# INPUT_OUTPUT_BOTTOM.net
KiCad netlist of a schematic drawn in EAGLE
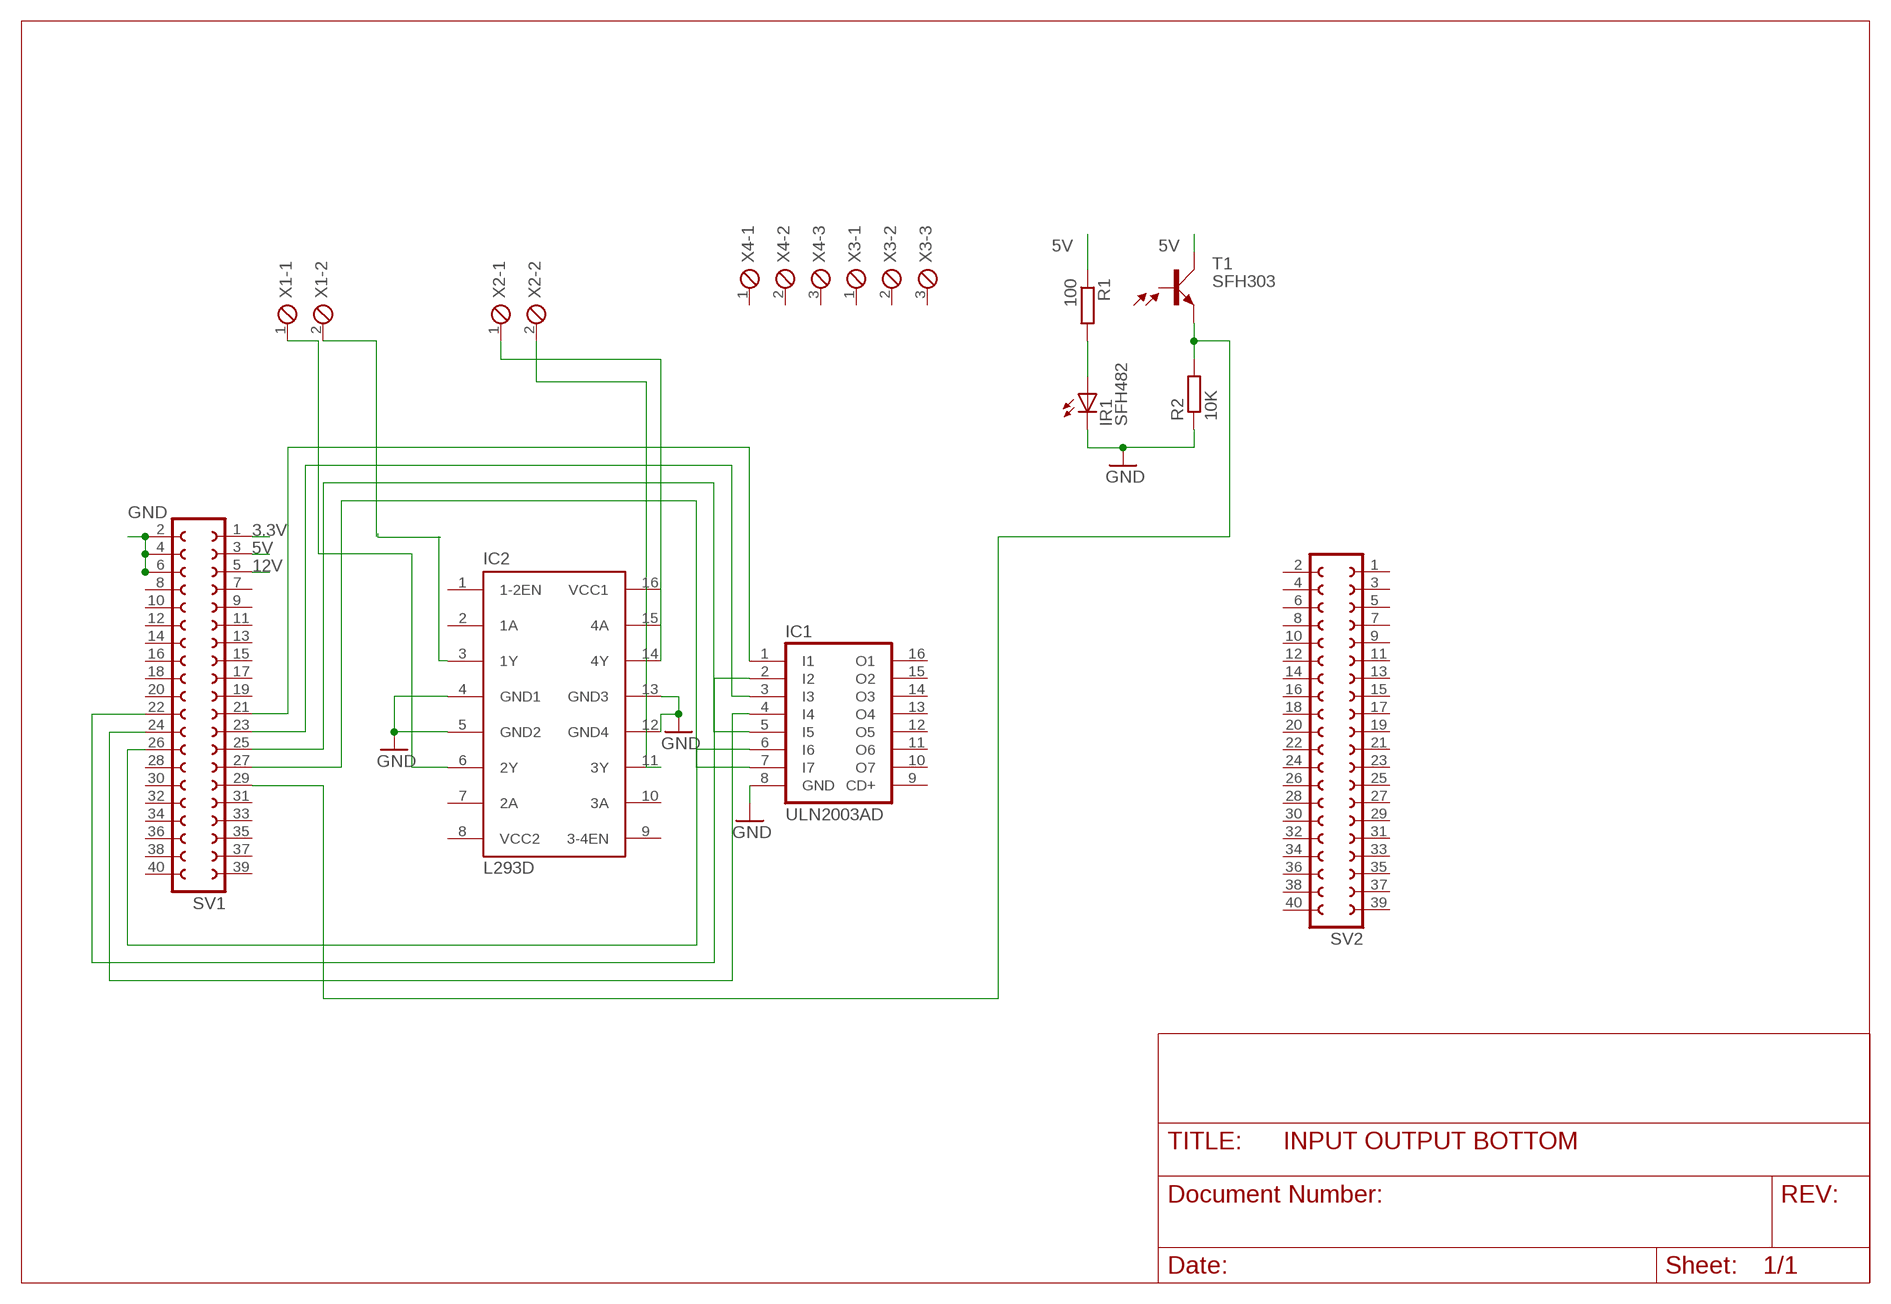
[diagram p0: schematic, sheet 1]

(export (version "E")
  (design (tool "Eeschema 10.0.6"))
  (components
    (comp (ref "IC1")
      (value "ULN2003AD")
      (footprint "eagle-import:SO16")
      (libsource (lib "eagle-import") (part "ULN2003AD"))
    )
    (comp (ref "IC2")
      (value "L293D")
      (footprint "eagle-import:DIL16")
      (libsource (lib "eagle-import") (part "L293D"))
    )
    (comp (ref "IR1")
      (value "SFH482")
      (footprint "eagle-import:SFH482")
      (libsource (lib "eagle-import") (part "SFH482"))
    )
    (comp (ref "R1")
      (value "100")
      (footprint "eagle-import:R3225")
      (libsource (lib "eagle-import") (part "R-EU_R3225"))
    )
    (comp (ref "R2")
      (value "10K")
      (footprint "eagle-import:R3225")
      (libsource (lib "eagle-import") (part "R-EU_R3225"))
    )
    (comp (ref "SV1")
      (value "FE20-2")
      (footprint "eagle-import:FE20-2")
      (libsource (lib "eagle-import") (part "FE20-2"))
    )
    (comp (ref "SV2")
      (value "FE20-2")
      (footprint "eagle-import:FE20-2")
      (libsource (lib "eagle-import") (part "FE20-2"))
    )
    (comp (ref "T1")
      (value "SFH303")
      (footprint "eagle-import:SFH303")
      (libsource (lib "eagle-import") (part "SFH303"))
    )
    (comp (ref "X1")
      (value "MPT2")
      (footprint "eagle-import:2POL254")
      (libsource (lib "eagle-import") (part "MPT2"))
    )
    (comp (ref "X2")
      (value "MPT2")
      (footprint "eagle-import:2POL254")
      (libsource (lib "eagle-import") (part "MPT2"))
    )
    (comp (ref "X3")
      (value "MPT3")
      (footprint "eagle-import:3POL254")
      (libsource (lib "eagle-import") (part "MPT3"))
    )
    (comp (ref "X4")
      (value "MPT3")
      (footprint "eagle-import:3POL254")
      (libsource (lib "eagle-import") (part "MPT3"))
    )
  )
  (nets
    (net (code "1") (name "/3.3V") (class "Default")
      (node (ref "SV1") (pin "1") (pinfunction "1_1") (pintype "passive"))
    )
    (net (code "2") (name "/5V") (class "Default")
      (node (ref "R1") (pin "1") (pinfunction "1_1") (pintype "passive"))
      (node (ref "SV1") (pin "3") (pinfunction "3_3") (pintype "passive"))
      (node (ref "T1") (pin "2") (pinfunction "C_2") (pintype "passive"))
    )
    (net (code "3") (name "/12V") (class "Default")
      (node (ref "SV1") (pin "5") (pinfunction "5_5") (pintype "passive"))
    )
    (net (code "4") (name "/VCC1") (class "Default")
      (node (ref "IC2") (pin "16") (pinfunction "VCC1_16") (pintype "power_in"))
    )
    (net (code "5") (name "/VCC2") (class "Default")
      (node (ref "IC2") (pin "8") (pinfunction "VCC2_8") (pintype "power_in"))
    )
    (net (code "6") (name "GND") (class "Default")
      (node (ref "IC1") (pin "8") (pinfunction "GND_8") (pintype "power_in"))
      (node (ref "IC2") (pin "12") (pinfunction "GND4_12") (pintype "power_in"))
      (node (ref "IC2") (pin "13") (pinfunction "GND3_13") (pintype "power_in"))
      (node (ref "IC2") (pin "4") (pinfunction "GND1_4") (pintype "power_in"))
      (node (ref "IC2") (pin "5") (pinfunction "GND2_5") (pintype "power_in"))
      (node (ref "IR1") (pin "K") (pinfunction "C_K") (pintype "passive"))
      (node (ref "R2") (pin "1") (pinfunction "1_1") (pintype "passive"))
      (node (ref "SV1") (pin "2") (pinfunction "2_2") (pintype "passive"))
      (node (ref "SV1") (pin "4") (pinfunction "4_4") (pintype "passive"))
      (node (ref "SV1") (pin "6") (pinfunction "6_6") (pintype "passive"))
    )
    (net (code "7") (name "Net-(IC1-I1)") (class "Default")
      (node (ref "IC1") (pin "1") (pinfunction "I1_1") (pintype "input"))
      (node (ref "SV1") (pin "21") (pinfunction "21_21") (pintype "passive"))
    )
    (net (code "8") (name "Net-(IC1-I2)") (class "Default")
      (node (ref "IC1") (pin "2") (pinfunction "I2_2") (pintype "input"))
      (node (ref "SV1") (pin "22") (pinfunction "22_22") (pintype "passive"))
    )
    (net (code "9") (name "Net-(IC1-I3)") (class "Default")
      (node (ref "IC1") (pin "3") (pinfunction "I3_3") (pintype "input"))
      (node (ref "SV1") (pin "23") (pinfunction "23_23") (pintype "passive"))
    )
    (net (code "10") (name "Net-(IC1-I4)") (class "Default")
      (node (ref "IC1") (pin "4") (pinfunction "I4_4") (pintype "input"))
      (node (ref "SV1") (pin "24") (pinfunction "24_24") (pintype "passive"))
    )
    (net (code "11") (name "Net-(IC1-I5)") (class "Default")
      (node (ref "IC1") (pin "5") (pinfunction "I5_5") (pintype "input"))
      (node (ref "SV1") (pin "25") (pinfunction "25_25") (pintype "passive"))
    )
    (net (code "12") (name "Net-(IC1-I6)") (class "Default")
      (node (ref "IC1") (pin "6") (pinfunction "I6_6") (pintype "input"))
      (node (ref "SV1") (pin "26") (pinfunction "26_26") (pintype "passive"))
    )
    (net (code "13") (name "Net-(IC1-I7)") (class "Default")
      (node (ref "IC1") (pin "7") (pinfunction "I7_7") (pintype "input"))
      (node (ref "SV1") (pin "27") (pinfunction "27_27") (pintype "passive"))
    )
    (net (code "14") (name "Net-(IC2-2Y)") (class "Default")
      (node (ref "IC2") (pin "6") (pinfunction "2Y_6") (pintype "output"))
      (node (ref "X1") (pin "1") (pinfunction "1_1") (pintype "passive"))
    )
    (net (code "15") (name "Net-(IC2-3Y)") (class "Default")
      (node (ref "IC2") (pin "11") (pinfunction "3Y_11") (pintype "output"))
      (node (ref "X2") (pin "2") (pinfunction "1_2") (pintype "passive"))
    )
    (net (code "16") (name "Net-(IC2-4Y)") (class "Default")
      (node (ref "IC2") (pin "14") (pinfunction "4Y_14") (pintype "output"))
      (node (ref "X2") (pin "1") (pinfunction "1_1") (pintype "passive"))
    )
    (net (code "17") (name "Net-(IR1-PadA)") (class "Default")
      (node (ref "IR1") (pin "A") (pinfunction "A_A") (pintype "passive"))
      (node (ref "R1") (pin "2") (pinfunction "2_2") (pintype "passive"))
    )
    (net (code "18") (name "Net-(T1-E)") (class "Default")
      (node (ref "R2") (pin "2") (pinfunction "2_2") (pintype "passive"))
      (node (ref "SV1") (pin "29") (pinfunction "29_29") (pintype "passive"))
      (node (ref "T1") (pin "1") (pinfunction "E_1") (pintype "passive"))
    )
    (net (code "19") (name "unconnected-(IC1-CD+-Pad9)") (class "Default")
      (node (ref "IC1") (pin "9") (pinfunction "CD+_9") (pintype "passive"))
    )
    (net (code "20") (name "unconnected-(IC1-O1-Pad16)") (class "Default")
      (node (ref "IC1") (pin "16") (pinfunction "O1_16") (pintype "open_collector"))
    )
    (net (code "21") (name "unconnected-(IC1-O2-Pad15)") (class "Default")
      (node (ref "IC1") (pin "15") (pinfunction "O2_15") (pintype "open_collector"))
    )
    (net (code "22") (name "unconnected-(IC1-O3-Pad14)") (class "Default")
      (node (ref "IC1") (pin "14") (pinfunction "O3_14") (pintype "open_collector"))
    )
    (net (code "23") (name "unconnected-(IC1-O4-Pad13)") (class "Default")
      (node (ref "IC1") (pin "13") (pinfunction "O4_13") (pintype "open_collector"))
    )
    (net (code "24") (name "unconnected-(IC1-O5-Pad12)") (class "Default")
      (node (ref "IC1") (pin "12") (pinfunction "O5_12") (pintype "open_collector"))
    )
    (net (code "25") (name "unconnected-(IC1-O6-Pad11)") (class "Default")
      (node (ref "IC1") (pin "11") (pinfunction "O6_11") (pintype "open_collector"))
    )
    (net (code "26") (name "unconnected-(IC1-O7-Pad10)") (class "Default")
      (node (ref "IC1") (pin "10") (pinfunction "O7_10") (pintype "open_collector"))
    )
    (net (code "27") (name "unconnected-(IC2-1-2EN-Pad1)") (class "Default")
      (node (ref "IC2") (pin "1") (pinfunction "1-2EN_1") (pintype "input"))
    )
    (net (code "28") (name "unconnected-(IC2-1A-Pad2)") (class "Default")
      (node (ref "IC2") (pin "2") (pinfunction "1A_2") (pintype "input"))
    )
    (net (code "29") (name "unconnected-(IC2-1Y-Pad3)") (class "Default")
      (node (ref "IC2") (pin "3") (pinfunction "1Y_3") (pintype "output"))
    )
    (net (code "30") (name "unconnected-(IC2-2A-Pad7)") (class "Default")
      (node (ref "IC2") (pin "7") (pinfunction "2A_7") (pintype "input"))
    )
    (net (code "31") (name "unconnected-(IC2-3-4EN-Pad9)") (class "Default")
      (node (ref "IC2") (pin "9") (pinfunction "3-4EN_9") (pintype "input"))
    )
    (net (code "32") (name "unconnected-(IC2-3A-Pad10)") (class "Default")
      (node (ref "IC2") (pin "10") (pinfunction "3A_10") (pintype "input"))
    )
    (net (code "33") (name "unconnected-(IC2-4A-Pad15)") (class "Default")
      (node (ref "IC2") (pin "15") (pinfunction "4A_15") (pintype "input"))
    )
    (net (code "34") (name "unconnected-(SV1-Pad7)") (class "Default")
      (node (ref "SV1") (pin "7") (pinfunction "7_7") (pintype "passive"))
    )
    (net (code "35") (name "unconnected-(SV1-Pad8)") (class "Default")
      (node (ref "SV1") (pin "8") (pinfunction "8_8") (pintype "passive"))
    )
    (net (code "36") (name "unconnected-(SV1-Pad9)") (class "Default")
      (node (ref "SV1") (pin "9") (pinfunction "9_9") (pintype "passive"))
    )
    (net (code "37") (name "unconnected-(SV1-Pad10)") (class "Default")
      (node (ref "SV1") (pin "10") (pinfunction "10_10") (pintype "passive"))
    )
    (net (code "38") (name "unconnected-(SV1-Pad11)") (class "Default")
      (node (ref "SV1") (pin "11") (pinfunction "11_11") (pintype "passive"))
    )
    (net (code "39") (name "unconnected-(SV1-Pad12)") (class "Default")
      (node (ref "SV1") (pin "12") (pinfunction "12_12") (pintype "passive"))
    )
    (net (code "40") (name "unconnected-(SV1-Pad13)") (class "Default")
      (node (ref "SV1") (pin "13") (pinfunction "13_13") (pintype "passive"))
    )
    (net (code "41") (name "unconnected-(SV1-Pad14)") (class "Default")
      (node (ref "SV1") (pin "14") (pinfunction "14_14") (pintype "passive"))
    )
    (net (code "42") (name "unconnected-(SV1-Pad15)") (class "Default")
      (node (ref "SV1") (pin "15") (pinfunction "15_15") (pintype "passive"))
    )
    (net (code "43") (name "unconnected-(SV1-Pad16)") (class "Default")
      (node (ref "SV1") (pin "16") (pinfunction "16_16") (pintype "passive"))
    )
    (net (code "44") (name "unconnected-(SV1-Pad17)") (class "Default")
      (node (ref "SV1") (pin "17") (pinfunction "17_17") (pintype "passive"))
    )
    (net (code "45") (name "unconnected-(SV1-Pad18)") (class "Default")
      (node (ref "SV1") (pin "18") (pinfunction "18_18") (pintype "passive"))
    )
    (net (code "46") (name "unconnected-(SV1-Pad19)") (class "Default")
      (node (ref "SV1") (pin "19") (pinfunction "19_19") (pintype "passive"))
    )
    (net (code "47") (name "unconnected-(SV1-Pad20)") (class "Default")
      (node (ref "SV1") (pin "20") (pinfunction "20_20") (pintype "passive"))
    )
    (net (code "48") (name "unconnected-(SV1-Pad28)") (class "Default")
      (node (ref "SV1") (pin "28") (pinfunction "28_28") (pintype "passive"))
    )
    (net (code "49") (name "unconnected-(SV1-Pad30)") (class "Default")
      (node (ref "SV1") (pin "30") (pinfunction "30_30") (pintype "passive"))
    )
    (net (code "50") (name "unconnected-(SV1-Pad31)") (class "Default")
      (node (ref "SV1") (pin "31") (pinfunction "31_31") (pintype "passive"))
    )
    (net (code "51") (name "unconnected-(SV1-Pad32)") (class "Default")
      (node (ref "SV1") (pin "32") (pinfunction "32_32") (pintype "passive"))
    )
    (net (code "52") (name "unconnected-(SV1-Pad33)") (class "Default")
      (node (ref "SV1") (pin "33") (pinfunction "33_33") (pintype "passive"))
    )
    (net (code "53") (name "unconnected-(SV1-Pad34)") (class "Default")
      (node (ref "SV1") (pin "34") (pinfunction "34_34") (pintype "passive"))
    )
    (net (code "54") (name "unconnected-(SV1-Pad35)") (class "Default")
      (node (ref "SV1") (pin "35") (pinfunction "35_35") (pintype "passive"))
    )
    (net (code "55") (name "unconnected-(SV1-Pad36)") (class "Default")
      (node (ref "SV1") (pin "36") (pinfunction "36_36") (pintype "passive"))
    )
    (net (code "56") (name "unconnected-(SV1-Pad37)") (class "Default")
      (node (ref "SV1") (pin "37") (pinfunction "37_37") (pintype "passive"))
    )
    (net (code "57") (name "unconnected-(SV1-Pad38)") (class "Default")
      (node (ref "SV1") (pin "38") (pinfunction "38_38") (pintype "passive"))
    )
    (net (code "58") (name "unconnected-(SV1-Pad39)") (class "Default")
      (node (ref "SV1") (pin "39") (pinfunction "39_39") (pintype "passive"))
    )
    (net (code "59") (name "unconnected-(SV1-Pad40)") (class "Default")
      (node (ref "SV1") (pin "40") (pinfunction "40_40") (pintype "passive"))
    )
    (net (code "60") (name "unconnected-(SV2-Pad1)") (class "Default")
      (node (ref "SV2") (pin "1") (pinfunction "1_1") (pintype "passive"))
    )
    (net (code "61") (name "unconnected-(SV2-Pad2)") (class "Default")
      (node (ref "SV2") (pin "2") (pinfunction "2_2") (pintype "passive"))
    )
    (net (code "62") (name "unconnected-(SV2-Pad3)") (class "Default")
      (node (ref "SV2") (pin "3") (pinfunction "3_3") (pintype "passive"))
    )
    (net (code "63") (name "unconnected-(SV2-Pad4)") (class "Default")
      (node (ref "SV2") (pin "4") (pinfunction "4_4") (pintype "passive"))
    )
    (net (code "64") (name "unconnected-(SV2-Pad5)") (class "Default")
      (node (ref "SV2") (pin "5") (pinfunction "5_5") (pintype "passive"))
    )
    (net (code "65") (name "unconnected-(SV2-Pad6)") (class "Default")
      (node (ref "SV2") (pin "6") (pinfunction "6_6") (pintype "passive"))
    )
    (net (code "66") (name "unconnected-(SV2-Pad7)") (class "Default")
      (node (ref "SV2") (pin "7") (pinfunction "7_7") (pintype "passive"))
    )
    (net (code "67") (name "unconnected-(SV2-Pad8)") (class "Default")
      (node (ref "SV2") (pin "8") (pinfunction "8_8") (pintype "passive"))
    )
    (net (code "68") (name "unconnected-(SV2-Pad9)") (class "Default")
      (node (ref "SV2") (pin "9") (pinfunction "9_9") (pintype "passive"))
    )
    (net (code "69") (name "unconnected-(SV2-Pad10)") (class "Default")
      (node (ref "SV2") (pin "10") (pinfunction "10_10") (pintype "passive"))
    )
    (net (code "70") (name "unconnected-(SV2-Pad11)") (class "Default")
      (node (ref "SV2") (pin "11") (pinfunction "11_11") (pintype "passive"))
    )
    (net (code "71") (name "unconnected-(SV2-Pad12)") (class "Default")
      (node (ref "SV2") (pin "12") (pinfunction "12_12") (pintype "passive"))
    )
    (net (code "72") (name "unconnected-(SV2-Pad13)") (class "Default")
      (node (ref "SV2") (pin "13") (pinfunction "13_13") (pintype "passive"))
    )
    (net (code "73") (name "unconnected-(SV2-Pad14)") (class "Default")
      (node (ref "SV2") (pin "14") (pinfunction "14_14") (pintype "passive"))
    )
    (net (code "74") (name "unconnected-(SV2-Pad15)") (class "Default")
      (node (ref "SV2") (pin "15") (pinfunction "15_15") (pintype "passive"))
    )
    (net (code "75") (name "unconnected-(SV2-Pad16)") (class "Default")
      (node (ref "SV2") (pin "16") (pinfunction "16_16") (pintype "passive"))
    )
    (net (code "76") (name "unconnected-(SV2-Pad17)") (class "Default")
      (node (ref "SV2") (pin "17") (pinfunction "17_17") (pintype "passive"))
    )
    (net (code "77") (name "unconnected-(SV2-Pad18)") (class "Default")
      (node (ref "SV2") (pin "18") (pinfunction "18_18") (pintype "passive"))
    )
    (net (code "78") (name "unconnected-(SV2-Pad19)") (class "Default")
      (node (ref "SV2") (pin "19") (pinfunction "19_19") (pintype "passive"))
    )
    (net (code "79") (name "unconnected-(SV2-Pad20)") (class "Default")
      (node (ref "SV2") (pin "20") (pinfunction "20_20") (pintype "passive"))
    )
    (net (code "80") (name "unconnected-(SV2-Pad21)") (class "Default")
      (node (ref "SV2") (pin "21") (pinfunction "21_21") (pintype "passive"))
    )
    (net (code "81") (name "unconnected-(SV2-Pad22)") (class "Default")
      (node (ref "SV2") (pin "22") (pinfunction "22_22") (pintype "passive"))
    )
    (net (code "82") (name "unconnected-(SV2-Pad23)") (class "Default")
      (node (ref "SV2") (pin "23") (pinfunction "23_23") (pintype "passive"))
    )
    (net (code "83") (name "unconnected-(SV2-Pad24)") (class "Default")
      (node (ref "SV2") (pin "24") (pinfunction "24_24") (pintype "passive"))
    )
    (net (code "84") (name "unconnected-(SV2-Pad25)") (class "Default")
      (node (ref "SV2") (pin "25") (pinfunction "25_25") (pintype "passive"))
    )
    (net (code "85") (name "unconnected-(SV2-Pad26)") (class "Default")
      (node (ref "SV2") (pin "26") (pinfunction "26_26") (pintype "passive"))
    )
    (net (code "86") (name "unconnected-(SV2-Pad27)") (class "Default")
      (node (ref "SV2") (pin "27") (pinfunction "27_27") (pintype "passive"))
    )
    (net (code "87") (name "unconnected-(SV2-Pad28)") (class "Default")
      (node (ref "SV2") (pin "28") (pinfunction "28_28") (pintype "passive"))
    )
    (net (code "88") (name "unconnected-(SV2-Pad29)") (class "Default")
      (node (ref "SV2") (pin "29") (pinfunction "29_29") (pintype "passive"))
    )
    (net (code "89") (name "unconnected-(SV2-Pad30)") (class "Default")
      (node (ref "SV2") (pin "30") (pinfunction "30_30") (pintype "passive"))
    )
    (net (code "90") (name "unconnected-(SV2-Pad31)") (class "Default")
      (node (ref "SV2") (pin "31") (pinfunction "31_31") (pintype "passive"))
    )
    (net (code "91") (name "unconnected-(SV2-Pad32)") (class "Default")
      (node (ref "SV2") (pin "32") (pinfunction "32_32") (pintype "passive"))
    )
    (net (code "92") (name "unconnected-(SV2-Pad33)") (class "Default")
      (node (ref "SV2") (pin "33") (pinfunction "33_33") (pintype "passive"))
    )
    (net (code "93") (name "unconnected-(SV2-Pad34)") (class "Default")
      (node (ref "SV2") (pin "34") (pinfunction "34_34") (pintype "passive"))
    )
    (net (code "94") (name "unconnected-(SV2-Pad35)") (class "Default")
      (node (ref "SV2") (pin "35") (pinfunction "35_35") (pintype "passive"))
    )
    (net (code "95") (name "unconnected-(SV2-Pad36)") (class "Default")
      (node (ref "SV2") (pin "36") (pinfunction "36_36") (pintype "passive"))
    )
    (net (code "96") (name "unconnected-(SV2-Pad37)") (class "Default")
      (node (ref "SV2") (pin "37") (pinfunction "37_37") (pintype "passive"))
    )
    (net (code "97") (name "unconnected-(SV2-Pad38)") (class "Default")
      (node (ref "SV2") (pin "38") (pinfunction "38_38") (pintype "passive"))
    )
    (net (code "98") (name "unconnected-(SV2-Pad39)") (class "Default")
      (node (ref "SV2") (pin "39") (pinfunction "39_39") (pintype "passive"))
    )
    (net (code "99") (name "unconnected-(SV2-Pad40)") (class "Default")
      (node (ref "SV2") (pin "40") (pinfunction "40_40") (pintype "passive"))
    )
    (net (code "100") (name "unconnected-(T1-B-Pad3)") (class "Default")
      (node (ref "T1") (pin "3") (pinfunction "B_3") (pintype "passive"))
    )
    (net (code "101") (name "unconnected-(X1B-1-Pad2)") (class "Default")
      (node (ref "X1") (pin "2") (pinfunction "1_2") (pintype "passive"))
    )
    (net (code "102") (name "unconnected-(X3-Pad1)") (class "Default")
      (node (ref "X3") (pin "1") (pinfunction "1_1") (pintype "passive"))
    )
    (net (code "103") (name "unconnected-(X3B-1-Pad2)") (class "Default")
      (node (ref "X3") (pin "2") (pinfunction "1_2") (pintype "passive"))
    )
    (net (code "104") (name "unconnected-(X3C-1-Pad3)") (class "Default")
      (node (ref "X3") (pin "3") (pinfunction "1_3") (pintype "passive"))
    )
    (net (code "105") (name "unconnected-(X4-Pad1)") (class "Default")
      (node (ref "X4") (pin "1") (pinfunction "1_1") (pintype "passive"))
    )
    (net (code "106") (name "unconnected-(X4B-1-Pad2)") (class "Default")
      (node (ref "X4") (pin "2") (pinfunction "1_2") (pintype "passive"))
    )
    (net (code "107") (name "unconnected-(X4C-1-Pad3)") (class "Default")
      (node (ref "X4") (pin "3") (pinfunction "1_3") (pintype "passive"))
    )
  )
)
